# ldrboard.net
KiCad netlist of a schematic drawn in EAGLE
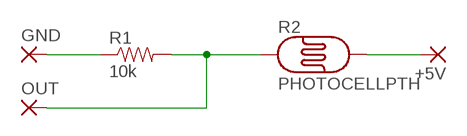
[diagram p0: schematic, sheet 1]

(export (version "E")
  (design (tool "Eeschema 10.0.6"))
  (components
    (comp (ref "+5V")
      (value "2,54/1,1")
      (footprint "eagle-import:2,54_1,1")
      (libsource (lib "eagle-import") (part "2,54/1,1"))
    )
    (comp (ref "GND")
      (value "2,54/1,1")
      (footprint "eagle-import:2,54_1,1")
      (libsource (lib "eagle-import") (part "2,54/1,1"))
    )
    (comp (ref "OUT")
      (value "2,54/1,1")
      (footprint "eagle-import:2,54_1,1")
      (libsource (lib "eagle-import") (part "2,54/1,1"))
    )
    (comp (ref "R1")
      (value "10k")
      (footprint "eagle-import:AXIAL-0.3")
      (libsource (lib "eagle-import") (part "10KOHM-1/4W-1%(PTH)HORIZ"))
    )
    (comp (ref "R2")
      (value "PHOTOCELLPTH")
      (footprint "eagle-import:PHOTOCELL")
      (libsource (lib "eagle-import") (part "PHOTOCELLPTH"))
    )
  )
  (nets
    (net (code "1") (name "Net-(+5V-P)") (class "Default")
      (node (ref "+5V") (pin "1") (pinfunction "P_1") (pintype "passive"))
      (node (ref "R2") (pin "2") (pinfunction "P$2_2") (pintype "bidirectional"))
    )
    (net (code "2") (name "Net-(GND-P)") (class "Default")
      (node (ref "GND") (pin "1") (pinfunction "P_1") (pintype "passive"))
      (node (ref "R1") (pin "P$1") (pinfunction "1_P$1") (pintype "passive"))
    )
    (net (code "3") (name "Net-(OUT-P)") (class "Default")
      (node (ref "OUT") (pin "1") (pinfunction "P_1") (pintype "passive"))
      (node (ref "R1") (pin "P$2") (pinfunction "2_P$2") (pintype "passive"))
      (node (ref "R2") (pin "1") (pinfunction "P$1_1") (pintype "bidirectional"))
    )
  )
)
